# Optisk_Mottaker.net
KiCad netlist of a schematic drawn in Altium Designer
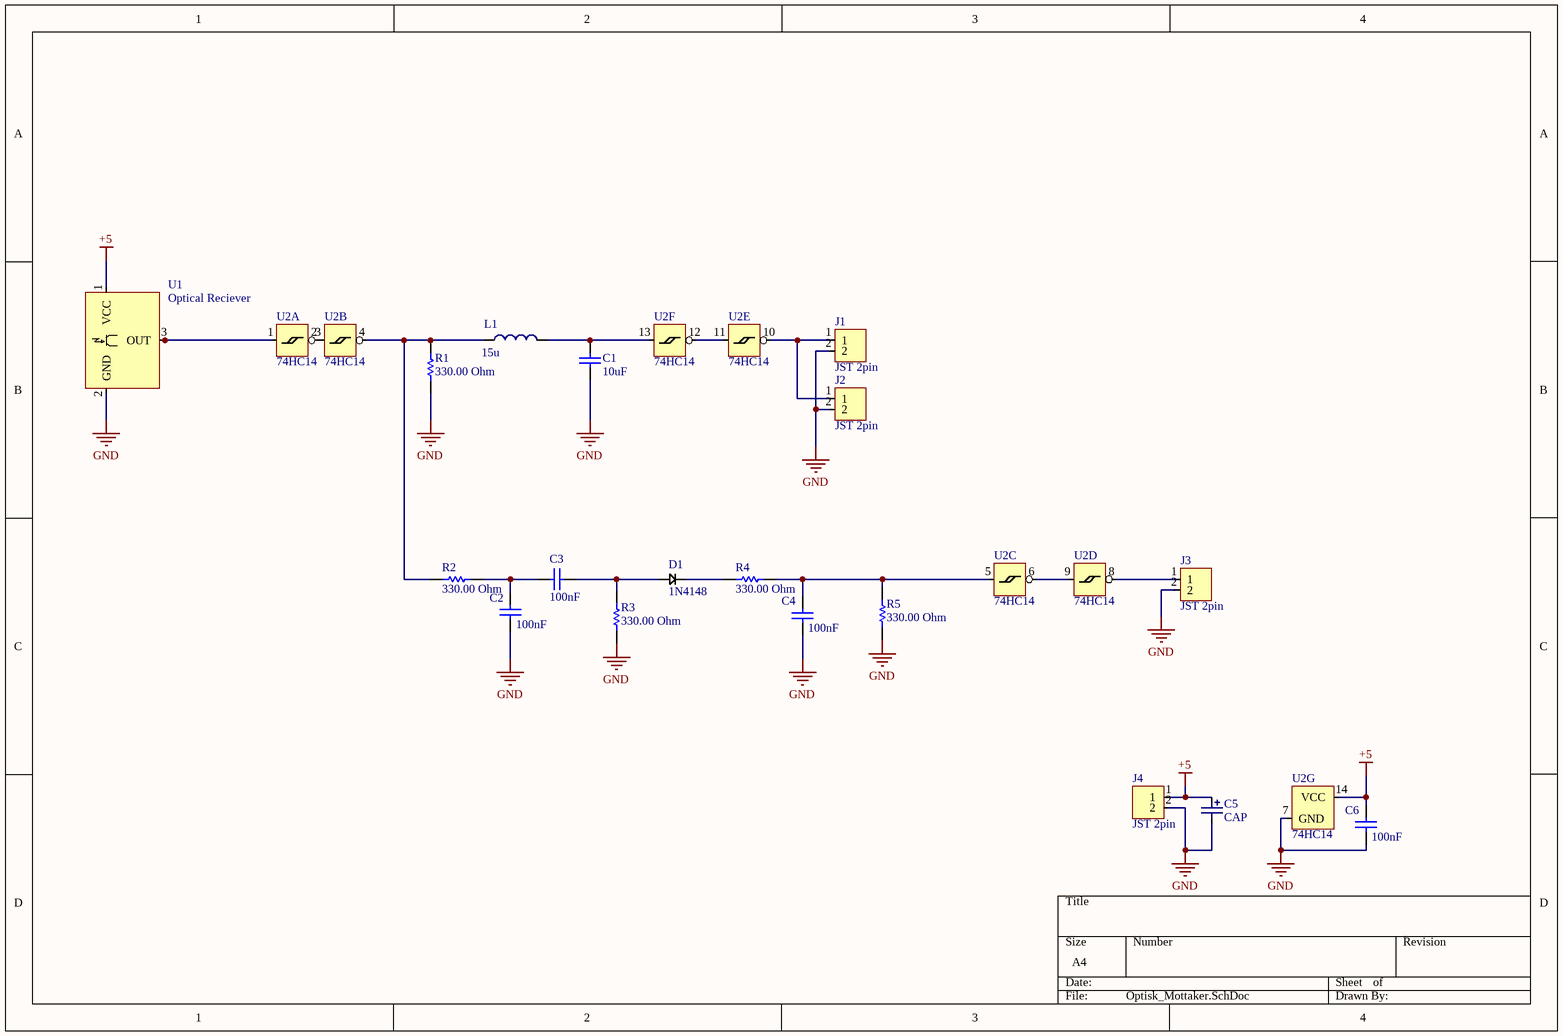
[diagram p0: Optisk_Mottaker.SchDoc]

(export (version "E")
  (design (tool "Eeschema 10.0.6"))
  (components
    (comp (ref "C1")
      (value "10uF")
      (footprint "CAPC1206(3216)190_L")
      (description "CAP 10uF 25V ±10% 1206 (3216 Metric) Thickness 1.9mm SMD")
      (fields (field (name "TOLERANCE") "±10%") (field (name "Comment") "CAP 10uF 25V 1206(3216)"))
      (libsource (lib "Altium Content Vault") (part "CAP"))
    )
    (comp (ref "C2")
      (value "100nF")
      (footprint "CAPC0805(2012)145_M")
      (description "CAP 100nF 25V ±5% 0805 (2012 Metric) Thickness 1.45mm SMD")
      (fields (field (name "TOLERANCE") "±5%") (field (name "Comment") "CAP 100nF 25V 0805(2012)"))
      (libsource (lib "Altium Content Vault") (part "CAP"))
    )
    (comp (ref "C3")
      (value "100nF")
      (footprint "CAPC0805(2012)145_M")
      (description "CAP 100nF 25V ±5% 0805 (2012 Metric) Thickness 1.45mm SMD")
      (fields (field (name "TOLERANCE") "±5%") (field (name "Comment") "CAP 100nF 25V 0805(2012)"))
      (libsource (lib "Altium Content Vault") (part "CAP"))
    )
    (comp (ref "C4")
      (value "100nF")
      (footprint "CAPC0805(2012)145_M")
      (description "CAP 100nF 25V ±5% 0805 (2012 Metric) Thickness 1.45mm SMD")
      (fields (field (name "TOLERANCE") "±5%") (field (name "Comment") "CAP 100nF 25V 0805(2012)"))
      (libsource (lib "Altium Content Vault") (part "CAP"))
    )
    (comp (ref "C5") (value "CAP") (footprint "CAP 2.5mm") (libsource (lib "Schlib1") (part "CAP")))
    (comp (ref "C6")
      (value "100nF")
      (footprint "CAPC0805(2012)145_M")
      (description "CAP 100nF 25V ±5% 0805 (2012 Metric) Thickness 1.45mm SMD")
      (fields (field (name "TOLERANCE") "±5%") (field (name "Comment") "CAP 100nF 25V 0805(2012)"))
      (libsource (lib "Altium Content Vault") (part "CAP"))
    )
    (comp (ref "D1") (value "1N4148") (footprint "1N4148") (libsource (lib "Schlib1") (part "1N4148")))
    (comp (ref "J1") (value "JST 2pin") (footprint "JST 2pin") (libsource (lib "Schlib1") (part "JST 2pin")))
    (comp (ref "J2") (value "JST 2pin") (footprint "JST 2pin") (libsource (lib "Schlib1") (part "JST 2pin")))
    (comp (ref "J3") (value "JST 2pin") (footprint "JST 2pin") (libsource (lib "Schlib1") (part "JST 2pin")))
    (comp (ref "J4") (value "JST 2pin") (footprint "JST 2pin") (libsource (lib "") (part "JST 2pin_1")))
    (comp (ref "L1")
      (value "15u")
      (footprint "SMD4mm")
      (fields (field (name "Comment") "L"))
      (libsource (lib "Schlib1") (part "L"))
    )
    (comp (ref "R1")
      (value "330.00 Ohm")
      (footprint "RESC0805(2012)_L")
      (description "330R 0.125W 5% 0805 (2012 Metric)  SMD")
      (fields (field (name "TOLERANCE") "5 %") (field (name "POWER") "0.125 W"))
      (libsource (lib "Altium Content Vault") (part "RES"))
    )
    (comp (ref "R2")
      (value "330.00 Ohm")
      (footprint "RESC0805(2012)_L")
      (description "330R 0.125W 5% 0805 (2012 Metric)  SMD")
      (fields (field (name "TOLERANCE") "5 %") (field (name "POWER") "0.125 W"))
      (libsource (lib "Altium Content Vault") (part "RES"))
    )
    (comp (ref "R3")
      (value "330.00 Ohm")
      (footprint "RESC0805(2012)_L")
      (description "330R 0.125W 5% 0805 (2012 Metric)  SMD")
      (fields (field (name "TOLERANCE") "5 %") (field (name "POWER") "0.125 W"))
      (libsource (lib "Altium Content Vault") (part "RES"))
    )
    (comp (ref "R4")
      (value "330.00 Ohm")
      (footprint "RESC0805(2012)_L")
      (description "330R 0.125W 5% 0805 (2012 Metric)  SMD")
      (fields (field (name "TOLERANCE") "5 %") (field (name "POWER") "0.125 W"))
      (libsource (lib "Altium Content Vault") (part "RES"))
    )
    (comp (ref "R5")
      (value "330.00 Ohm")
      (footprint "RESC0805(2012)_L")
      (description "330R 0.125W 5% 0805 (2012 Metric)  SMD")
      (fields (field (name "TOLERANCE") "5 %") (field (name "POWER") "0.125 W"))
      (libsource (lib "Altium Content Vault") (part "RES"))
    )
    (comp (ref "U1")
      (value "Optical Reciever")
      (footprint "GP1FAV50TK")
      (libsource (lib "Schlib1") (part "Otical Reciever"))
    )
    (comp (ref "U2") (value "74HC14") (footprint "SOP14") (libsource (lib "Schlib1") (part "74HC14")))
  )
  (nets
    (net (code "1") (name "+5") (class "Default")
      (node (ref "C5") (pin "2") (pinfunction "2_2") (pintype "passive"))
      (node (ref "C6") (pin "2") (pinfunction "2_2") (pintype "passive"))
      (node (ref "J4") (pin "1") (pinfunction "1_1") (pintype "passive"))
      (node (ref "U1") (pin "1") (pinfunction "VCC_1") (pintype "passive"))
      (node (ref "U2") (pin "14") (pinfunction "VCC_14") (pintype "passive"))
    )
    (net (code "2") (name "GND") (class "Default")
      (node (ref "C1") (pin "1") (pinfunction "1_1") (pintype "passive"))
      (node (ref "C2") (pin "1") (pinfunction "1_1") (pintype "passive"))
      (node (ref "C4") (pin "1") (pinfunction "1_1") (pintype "passive"))
      (node (ref "C5") (pin "1") (pinfunction "1_1") (pintype "passive"))
      (node (ref "C6") (pin "1") (pinfunction "1_1") (pintype "passive"))
      (node (ref "J1") (pin "2") (pinfunction "2_2") (pintype "passive"))
      (node (ref "J2") (pin "2") (pinfunction "2_2") (pintype "passive"))
      (node (ref "J3") (pin "2") (pinfunction "2_2") (pintype "passive"))
      (node (ref "J4") (pin "2") (pinfunction "2_2") (pintype "passive"))
      (node (ref "R1") (pin "2") (pinfunction "2_2") (pintype "passive"))
      (node (ref "R3") (pin "1") (pinfunction "1_1") (pintype "passive"))
      (node (ref "R5") (pin "1") (pinfunction "1_1") (pintype "passive"))
      (node (ref "U1") (pin "2") (pinfunction "GND_2") (pintype "passive"))
      (node (ref "U2") (pin "7") (pinfunction "GND_7") (pintype "passive"))
    )
    (net (code "3") (name "Net-(C1-Pad2)") (class "Default")
      (node (ref "C1") (pin "2") (pinfunction "2_2") (pintype "passive"))
      (node (ref "L1") (pin "2") (pinfunction "2_2") (pintype "passive"))
      (node (ref "U2") (pin "13") (pinfunction "13_13") (pintype "passive"))
    )
    (net (code "4") (name "Net-(C2-Pad2)") (class "Default")
      (node (ref "C2") (pin "2") (pinfunction "2_2") (pintype "passive"))
      (node (ref "C3") (pin "2") (pinfunction "2_2") (pintype "passive"))
      (node (ref "R2") (pin "2") (pinfunction "2_2") (pintype "passive"))
    )
    (net (code "5") (name "Net-(C3-Pad1)") (class "Default")
      (node (ref "C3") (pin "1") (pinfunction "1_1") (pintype "passive"))
      (node (ref "D1") (pin "A") (pinfunction "A_A") (pintype "passive"))
      (node (ref "R3") (pin "2") (pinfunction "2_2") (pintype "passive"))
    )
    (net (code "6") (name "Net-(C4-Pad2)") (class "Default")
      (node (ref "C4") (pin "2") (pinfunction "2_2") (pintype "passive"))
      (node (ref "R4") (pin "2") (pinfunction "2_2") (pintype "passive"))
      (node (ref "R5") (pin "2") (pinfunction "2_2") (pintype "passive"))
      (node (ref "U2") (pin "5") (pinfunction "5_5") (pintype "passive"))
    )
    (net (code "7") (name "Net-(D1-PadK)") (class "Default")
      (node (ref "D1") (pin "K") (pinfunction "K_K") (pintype "passive"))
      (node (ref "R4") (pin "1") (pinfunction "1_1") (pintype "passive"))
    )
    (net (code "8") (name "Net-(J1-Pad1)") (class "Default")
      (node (ref "J1") (pin "1") (pinfunction "1_1") (pintype "passive"))
      (node (ref "J2") (pin "1") (pinfunction "1_1") (pintype "passive"))
      (node (ref "U2") (pin "10") (pinfunction "10_10") (pintype "passive"))
    )
    (net (code "9") (name "Net-(J3-Pad1)") (class "Default")
      (node (ref "J3") (pin "1") (pinfunction "1_1") (pintype "passive"))
      (node (ref "U2") (pin "8") (pinfunction "8_8") (pintype "passive"))
    )
    (net (code "10") (name "Net-(L1-Pad1)") (class "Default")
      (node (ref "L1") (pin "1") (pinfunction "1_1") (pintype "passive"))
      (node (ref "R1") (pin "1") (pinfunction "1_1") (pintype "passive"))
      (node (ref "R2") (pin "1") (pinfunction "1_1") (pintype "passive"))
      (node (ref "U2") (pin "4") (pinfunction "4_4") (pintype "passive"))
    )
    (net (code "11") (name "Net-(U1-OUT)") (class "Default")
      (node (ref "U1") (pin "3") (pinfunction "OUT_3") (pintype "passive"))
      (node (ref "U2") (pin "1") (pinfunction "1_1") (pintype "passive"))
    )
    (net (code "12") (name "Net-(U2-Pad2)") (class "Default")
      (node (ref "U2") (pin "2") (pinfunction "2_2") (pintype "passive"))
      (node (ref "U2") (pin "3") (pinfunction "3_3") (pintype "passive"))
    )
    (net (code "13") (name "Net-(U2-Pad6)") (class "Default")
      (node (ref "U2") (pin "6") (pinfunction "6_6") (pintype "passive"))
      (node (ref "U2") (pin "9") (pinfunction "9_9") (pintype "passive"))
    )
    (net (code "14") (name "Net-(U2-Pad11)") (class "Default")
      (node (ref "U2") (pin "11") (pinfunction "11_11") (pintype "passive"))
      (node (ref "U2") (pin "12") (pinfunction "12_12") (pintype "passive"))
    )
  )
)
